# PDC_Low_Current_Outputs.net
KiCad netlist of a schematic drawn in Altium Designer
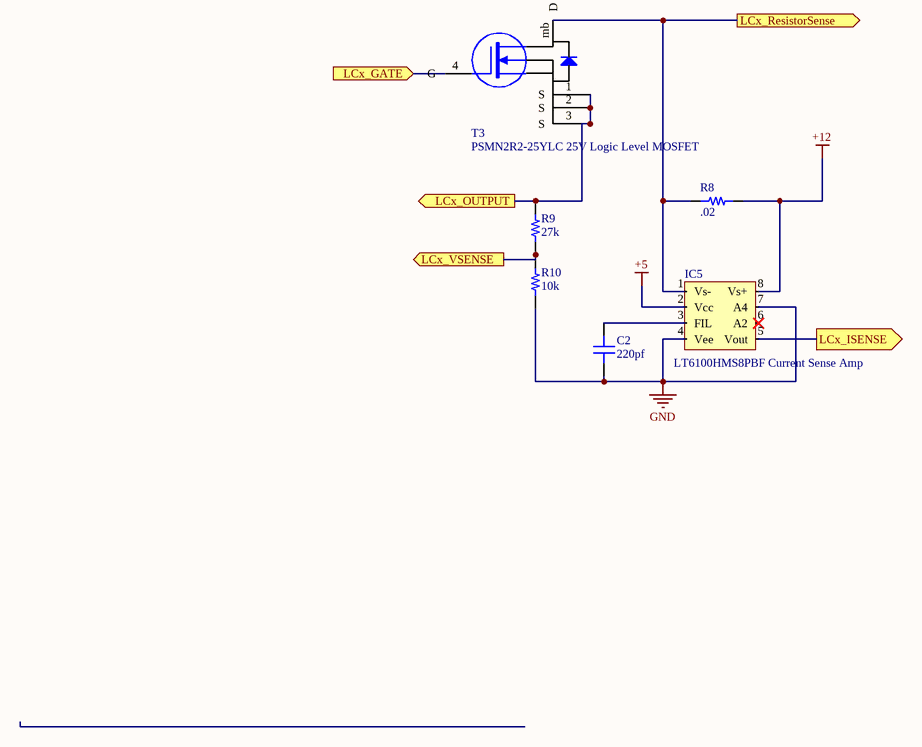
[diagram p0: PDC_Low_Current_Outputs.SchDoc]

(export (version "E")
  (design (tool "Eeschema 10.0.6"))
  (components
    (comp (ref "C2")
      (value "220pf")
      (footprint "CAP 0402/1005")
      (fields
        (field (name "Comment") "Capacitor MLCC 220pf 16V CAP 0402/1005")
        (field (name "CREATED_BY") "Nick Mah")
      )
      (libsource (lib "Altium-Lib") (part "Capacitor"))
    )
    (comp (ref "IC5")
      (value "LT6100HMS8PBF Current Sense Amp")
      (footprint "MSOP-8")
      (fields (field (name "CREATED_BY") "Eddy"))
      (libsource (lib "Altium-Lib") (part "LT6100HMS8PBF Current Sense Amp"))
    )
    (comp (ref "R8")
      (value ".02")
      (footprint "RES 2010/5025")
      (description "Current Sense Resistor")
      (fields (field (name "TOLERANCE") "1%") (field (name "POWER") "1W") (field (name "CREATED_BY") "Angel"))
      (libsource (lib "Altium-Lib") (part "Resistor"))
    )
    (comp (ref "R9")
      (value "27k")
      (footprint "RES 0805/2012")
      (fields
        (field (name "TOLERANCE") "10%")
        (field (name "POWER") "1/10W")
        (field (name "Comment") "Resistor 27k 0805 1/10W 10%")
        (field (name "CREATED_BY") "Nick Mah")
      )
      (libsource (lib "") (part "Resistor_1"))
    )
    (comp (ref "R10")
      (value "10k")
      (footprint "RES 0402/1005")
      (fields
        (field (name "TOLERANCE") "1%")
        (field (name "POWER") "1/10W")
        (field (name "Comment") "Resistor 10k 0402 1/10W 1%")
        (field (name "CREATED_BY") "Nick Mah")
      )
      (libsource (lib "") (part "Resistor_1"))
    )
    (comp (ref "T3")
      (value "PSMN2R2-25YLC 25V Logic Level MOSFET")
      (footprint "LFPAK-SO8")
      (description "N-Channel 25V 100A (Tc) 106W (Tc) Surface Mount LFPAK56, Power-SO8")
      (fields (field (name "MFRPARTNO") "PSMN2R2-25YLC,115") (field (name "CREATED_BY") "Nick"))
      (libsource (lib "Altium-Lib") (part "PSMN2R2-25YLC 25V Logic Level MOSFET"))
    )
  )
  (nets
    (net (code "1") (name "+5") (class "Default")
      (node (ref "IC5") (pin "2") (pinfunction "Vcc_2") (pintype "input"))
    )
    (net (code "2") (name "+12") (class "Default")
      (node (ref "IC5") (pin "8") (pinfunction "Vs+_8") (pintype "input"))
      (node (ref "R8") (pin "2") (pinfunction "2_2") (pintype "passive"))
    )
    (net (code "3") (name "/LCx_GATE") (class "Default")
      (node (ref "T3") (pin "4") (pinfunction "G_4") (pintype "passive"))
    )
    (net (code "4") (name "/LCx_ISENSE") (class "Default")
      (node (ref "IC5") (pin "5") (pinfunction "Vout_5") (pintype "input"))
    )
    (net (code "5") (name "/LCx_OUTPUT") (class "Default")
      (node (ref "R9") (pin "2") (pinfunction "2_2") (pintype "passive"))
      (node (ref "T3") (pin "1") (pinfunction "S_1") (pintype "passive"))
      (node (ref "T3") (pin "2") (pinfunction "S_2") (pintype "passive"))
      (node (ref "T3") (pin "3") (pinfunction "S_3") (pintype "passive"))
    )
    (net (code "6") (name "/LCx_ResistorSense") (class "Default")
      (node (ref "IC5") (pin "1") (pinfunction "Vs-_1") (pintype "input"))
      (node (ref "R8") (pin "1") (pinfunction "1_1") (pintype "passive"))
      (node (ref "T3") (pin "mb") (pinfunction "D_mb") (pintype "passive"))
    )
    (net (code "7") (name "/LCx_VSENSE") (class "Default")
      (node (ref "R10") (pin "2") (pinfunction "2_2") (pintype "passive"))
      (node (ref "R9") (pin "1") (pinfunction "1_1") (pintype "passive"))
    )
    (net (code "8") (name "GND") (class "Default")
      (node (ref "C2") (pin "1") (pinfunction "1_1") (pintype "passive"))
      (node (ref "IC5") (pin "4") (pinfunction "Vee_4") (pintype "input"))
      (node (ref "IC5") (pin "7") (pinfunction "A4_7") (pintype "input"))
      (node (ref "R10") (pin "1") (pinfunction "1_1") (pintype "passive"))
    )
    (net (code "9") (name "Net-(IC5-FIL)") (class "Default")
      (node (ref "C2") (pin "2") (pinfunction "2_2") (pintype "passive"))
      (node (ref "IC5") (pin "3") (pinfunction "FIL_3") (pintype "input"))
    )
    (net (code "10") (name "unconnected-(IC5-A2-Pad6)") (class "Default")
      (node (ref "IC5") (pin "6") (pinfunction "A2_6") (pintype "input+no_connect"))
    )
  )
)
